# adaptador_scart_v1_panelizado.net
KiCad netlist of a schematic drawn in EAGLE
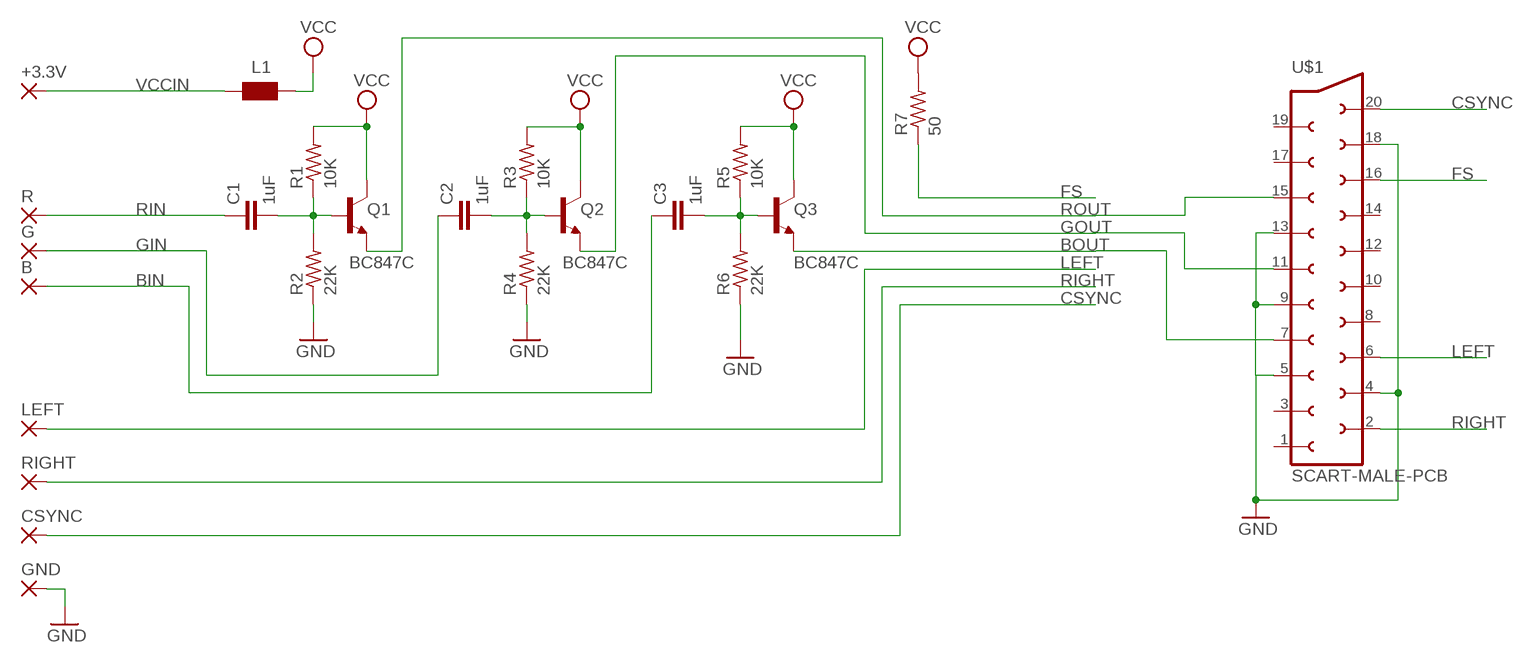
[diagram p0: schematic, sheet 1]

(export (version "E")
  (design (tool "Eeschema 10.0.6"))
  (components
    (comp (ref "+3.3V")
      (value "SMD2")
      (footprint "eagle-import:SMD1,27-2,54")
      (libsource (lib "eagle-import") (part "SMD2"))
    )
    (comp (ref "B")
      (value "SMD2")
      (footprint "eagle-import:SMD1,27-2,54")
      (libsource (lib "eagle-import") (part "SMD2"))
    )
    (comp (ref "C1")
      (value "1uF")
      (footprint "eagle-import:C1206K")
      (libsource (lib "eagle-import") (part "C-EUC1206K"))
    )
    (comp (ref "C2")
      (value "1uF")
      (footprint "eagle-import:C1206K")
      (libsource (lib "eagle-import") (part "C-EUC1206K"))
    )
    (comp (ref "C3")
      (value "1uF")
      (footprint "eagle-import:C1206K")
      (libsource (lib "eagle-import") (part "C-EUC1206K"))
    )
    (comp (ref "CSYNC")
      (value "SMD2")
      (footprint "eagle-import:SMD1,27-2,54")
      (libsource (lib "eagle-import") (part "SMD2"))
    )
    (comp (ref "G")
      (value "SMD2")
      (footprint "eagle-import:SMD1,27-2,54")
      (libsource (lib "eagle-import") (part "SMD2"))
    )
    (comp (ref "GND")
      (value "SMD2")
      (footprint "eagle-import:SMD1,27-2,54")
      (libsource (lib "eagle-import") (part "SMD2"))
    )
    (comp (ref "L1")
      (value "WE-CBF_0805")
      (footprint "eagle-import:0805")
      (libsource (lib "eagle-import") (part "WE-CBF_0805"))
    )
    (comp (ref "LEFT")
      (value "SMD2")
      (footprint "eagle-import:SMD1,27-2,54")
      (libsource (lib "eagle-import") (part "SMD2"))
    )
    (comp (ref "Q1")
      (value "BC847C")
      (footprint "eagle-import:SOT23")
      (libsource (lib "eagle-import") (part "BC847SMDC"))
    )
    (comp (ref "Q2")
      (value "BC847C")
      (footprint "eagle-import:SOT23")
      (libsource (lib "eagle-import") (part "BC847SMDC"))
    )
    (comp (ref "Q3")
      (value "BC847C")
      (footprint "eagle-import:SOT23")
      (libsource (lib "eagle-import") (part "BC847SMDC"))
    )
    (comp (ref "R")
      (value "SMD2")
      (footprint "eagle-import:SMD1,27-2,54")
      (libsource (lib "eagle-import") (part "SMD2"))
    )
    (comp (ref "R1")
      (value "10K")
      (footprint "eagle-import:R0805")
      (libsource (lib "eagle-import") (part "R-US_R0805"))
    )
    (comp (ref "R2")
      (value "22K")
      (footprint "eagle-import:R0805")
      (libsource (lib "eagle-import") (part "R-US_R0805"))
    )
    (comp (ref "R3")
      (value "10K")
      (footprint "eagle-import:R0805")
      (libsource (lib "eagle-import") (part "R-US_R0805"))
    )
    (comp (ref "R4")
      (value "22K")
      (footprint "eagle-import:R0805")
      (libsource (lib "eagle-import") (part "R-US_R0805"))
    )
    (comp (ref "R5")
      (value "10K")
      (footprint "eagle-import:R0805")
      (libsource (lib "eagle-import") (part "R-US_R0805"))
    )
    (comp (ref "R6")
      (value "22K")
      (footprint "eagle-import:R0805")
      (libsource (lib "eagle-import") (part "R-US_R0805"))
    )
    (comp (ref "R7")
      (value "50")
      (footprint "eagle-import:R0805")
      (libsource (lib "eagle-import") (part "R-US_R0805"))
    )
    (comp (ref "RIGHT")
      (value "SMD2")
      (footprint "eagle-import:SMD1,27-2,54")
      (libsource (lib "eagle-import") (part "SMD2"))
    )
    (comp (ref "U$1")
      (value "SCART-MALE-PCB")
      (footprint "eagle-import:SCART-PCB")
      (libsource (lib "eagle-import") (part "SCART-MALE-PCB"))
    )
  )
  (nets
    (net (code "1") (name "/BIN") (class "Default")
      (node (ref "B") (pin "1") (pinfunction "P_1") (pintype "passive"))
      (node (ref "C3") (pin "1") (pinfunction "1_1") (pintype "passive"))
    )
    (net (code "2") (name "/BOUT") (class "Default")
      (node (ref "Q3") (pin "2") (pinfunction "E_2") (pintype "passive"))
      (node (ref "U$1") (pin "7") (pinfunction "7_7") (pintype "passive"))
    )
    (net (code "3") (name "/CSYNC") (class "Default")
      (node (ref "CSYNC") (pin "1") (pinfunction "P_1") (pintype "passive"))
      (node (ref "U$1") (pin "20") (pinfunction "20_20") (pintype "passive"))
    )
    (net (code "4") (name "/FS") (class "Default")
      (node (ref "R7") (pin "1") (pinfunction "1_1") (pintype "passive"))
      (node (ref "U$1") (pin "16") (pinfunction "16_16") (pintype "passive"))
    )
    (net (code "5") (name "/GIN") (class "Default")
      (node (ref "C2") (pin "1") (pinfunction "1_1") (pintype "passive"))
      (node (ref "G") (pin "1") (pinfunction "P_1") (pintype "passive"))
    )
    (net (code "6") (name "/GOUT") (class "Default")
      (node (ref "Q2") (pin "2") (pinfunction "E_2") (pintype "passive"))
      (node (ref "U$1") (pin "11") (pinfunction "11_11") (pintype "passive"))
    )
    (net (code "7") (name "/LEFT") (class "Default")
      (node (ref "LEFT") (pin "1") (pinfunction "P_1") (pintype "passive"))
      (node (ref "U$1") (pin "6") (pinfunction "6_6") (pintype "passive"))
    )
    (net (code "8") (name "/RIGHT") (class "Default")
      (node (ref "RIGHT") (pin "1") (pinfunction "P_1") (pintype "passive"))
      (node (ref "U$1") (pin "2") (pinfunction "2_2") (pintype "passive"))
    )
    (net (code "9") (name "/RIN") (class "Default")
      (node (ref "C1") (pin "1") (pinfunction "1_1") (pintype "passive"))
      (node (ref "R") (pin "1") (pinfunction "P_1") (pintype "passive"))
    )
    (net (code "10") (name "/ROUT") (class "Default")
      (node (ref "Q1") (pin "2") (pinfunction "E_2") (pintype "passive"))
      (node (ref "U$1") (pin "15") (pinfunction "15_15") (pintype "passive"))
    )
    (net (code "11") (name "/VCCIN") (class "Default")
      (node (ref "+3.3V") (pin "1") (pinfunction "P_1") (pintype "passive"))
      (node (ref "L1") (pin "1") (pinfunction "1_1") (pintype "passive"))
    )
    (net (code "12") (name "GND") (class "Default")
      (node (ref "GND") (pin "1") (pinfunction "P_1") (pintype "passive"))
      (node (ref "R2") (pin "1") (pinfunction "1_1") (pintype "passive"))
      (node (ref "R4") (pin "1") (pinfunction "1_1") (pintype "passive"))
      (node (ref "R6") (pin "1") (pinfunction "1_1") (pintype "passive"))
      (node (ref "U$1") (pin "13") (pinfunction "13_13") (pintype "passive"))
      (node (ref "U$1") (pin "18") (pinfunction "18_18") (pintype "passive"))
      (node (ref "U$1") (pin "4") (pinfunction "4_4") (pintype "passive"))
      (node (ref "U$1") (pin "5") (pinfunction "5_5") (pintype "passive"))
      (node (ref "U$1") (pin "9") (pinfunction "9_9") (pintype "passive"))
    )
    (net (code "13") (name "Net-(Q1-B)") (class "Default")
      (node (ref "C1") (pin "2") (pinfunction "2_2") (pintype "passive"))
      (node (ref "Q1") (pin "1") (pinfunction "B_1") (pintype "passive"))
      (node (ref "R1") (pin "1") (pinfunction "1_1") (pintype "passive"))
      (node (ref "R2") (pin "2") (pinfunction "2_2") (pintype "passive"))
    )
    (net (code "14") (name "Net-(Q2-B)") (class "Default")
      (node (ref "C2") (pin "2") (pinfunction "2_2") (pintype "passive"))
      (node (ref "Q2") (pin "1") (pinfunction "B_1") (pintype "passive"))
      (node (ref "R3") (pin "1") (pinfunction "1_1") (pintype "passive"))
      (node (ref "R4") (pin "2") (pinfunction "2_2") (pintype "passive"))
    )
    (net (code "15") (name "Net-(Q3-B)") (class "Default")
      (node (ref "C3") (pin "2") (pinfunction "2_2") (pintype "passive"))
      (node (ref "Q3") (pin "1") (pinfunction "B_1") (pintype "passive"))
      (node (ref "R5") (pin "1") (pinfunction "1_1") (pintype "passive"))
      (node (ref "R6") (pin "2") (pinfunction "2_2") (pintype "passive"))
    )
    (net (code "16") (name "VCC") (class "Default")
      (node (ref "L1") (pin "2") (pinfunction "2_2") (pintype "passive"))
      (node (ref "Q1") (pin "3") (pinfunction "C_3") (pintype "passive"))
      (node (ref "Q2") (pin "3") (pinfunction "C_3") (pintype "passive"))
      (node (ref "Q3") (pin "3") (pinfunction "C_3") (pintype "passive"))
      (node (ref "R1") (pin "2") (pinfunction "2_2") (pintype "passive"))
      (node (ref "R3") (pin "2") (pinfunction "2_2") (pintype "passive"))
      (node (ref "R5") (pin "2") (pinfunction "2_2") (pintype "passive"))
      (node (ref "R7") (pin "2") (pinfunction "2_2") (pintype "passive"))
    )
    (net (code "17") (name "unconnected-(U$1-Pad1)") (class "Default")
      (node (ref "U$1") (pin "1") (pinfunction "1_1") (pintype "passive"))
    )
    (net (code "18") (name "unconnected-(U$1-Pad3)") (class "Default")
      (node (ref "U$1") (pin "3") (pinfunction "3_3") (pintype "passive"))
    )
    (net (code "19") (name "unconnected-(U$1-Pad8)") (class "Default")
      (node (ref "U$1") (pin "8") (pinfunction "8_8") (pintype "passive"))
    )
    (net (code "20") (name "unconnected-(U$1-Pad10)") (class "Default")
      (node (ref "U$1") (pin "10") (pinfunction "10_10") (pintype "passive"))
    )
    (net (code "21") (name "unconnected-(U$1-Pad12)") (class "Default")
      (node (ref "U$1") (pin "12") (pinfunction "12_12") (pintype "passive"))
    )
    (net (code "22") (name "unconnected-(U$1-Pad14)") (class "Default")
      (node (ref "U$1") (pin "14") (pinfunction "14_14") (pintype "passive"))
    )
    (net (code "23") (name "unconnected-(U$1-Pad17)") (class "Default")
      (node (ref "U$1") (pin "17") (pinfunction "17_17") (pintype "passive"))
    )
    (net (code "24") (name "unconnected-(U$1-Pad19)") (class "Default")
      (node (ref "U$1") (pin "19") (pinfunction "19_19") (pintype "passive"))
    )
  )
)
